# Controller.net
KiCad netlist of a schematic drawn in EAGLE
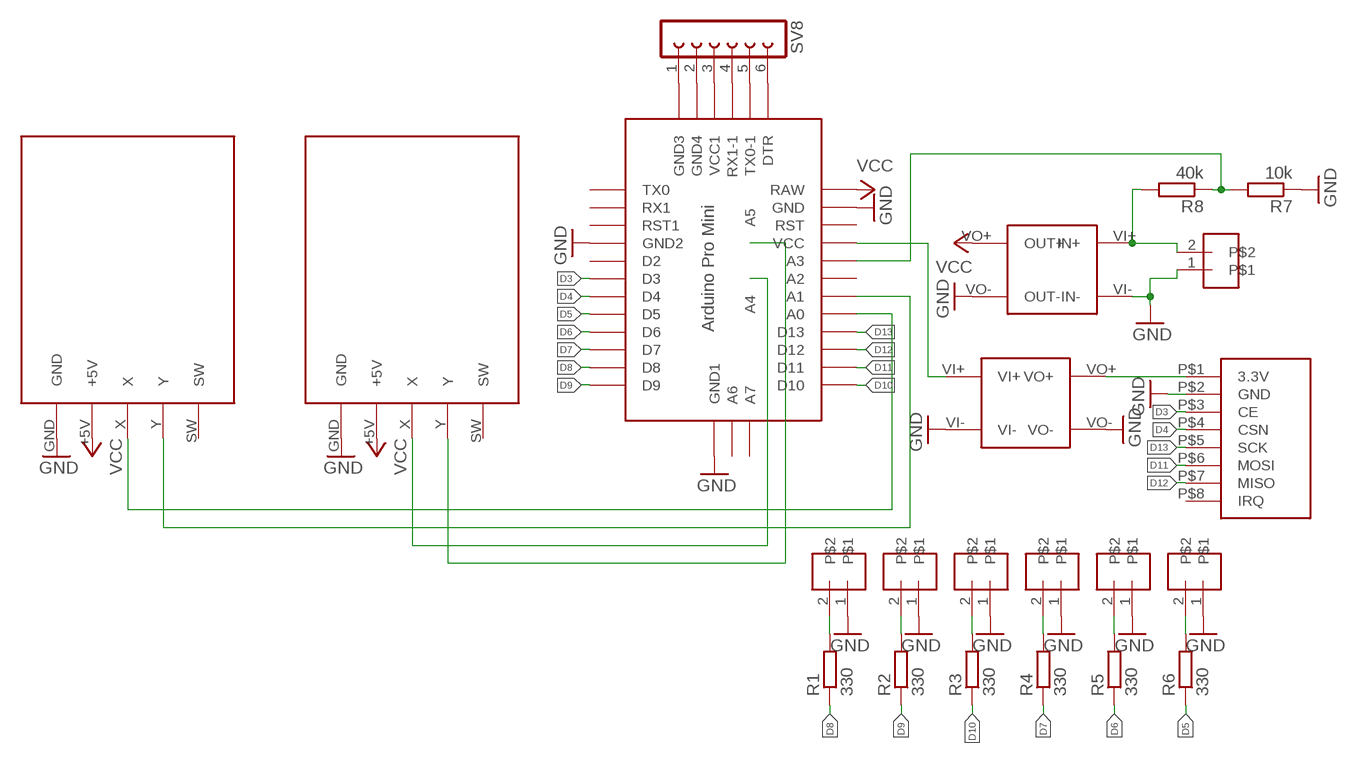
[diagram p0: schematic, sheet 1]

(export (version "E")
  (design (tool "Eeschema 10.0.6"))
  (components
    (comp (ref "R1")
      (value "330")
      (footprint "eagle-import:R1206")
      (libsource (lib "eagle-import") (part "R-EU_R1206"))
    )
    (comp (ref "R2")
      (value "330")
      (footprint "eagle-import:R1206")
      (libsource (lib "eagle-import") (part "R-EU_R1206"))
    )
    (comp (ref "R3")
      (value "330")
      (footprint "eagle-import:R1206")
      (libsource (lib "eagle-import") (part "R-EU_R1206"))
    )
    (comp (ref "R4")
      (value "330")
      (footprint "eagle-import:R1206")
      (libsource (lib "eagle-import") (part "R-EU_R1206"))
    )
    (comp (ref "R5")
      (value "330")
      (footprint "eagle-import:R1206")
      (libsource (lib "eagle-import") (part "R-EU_R1206"))
    )
    (comp (ref "R6")
      (value "330")
      (footprint "eagle-import:R1206")
      (libsource (lib "eagle-import") (part "R-EU_R1206"))
    )
    (comp (ref "R7")
      (value "10k")
      (footprint "eagle-import:R1206")
      (libsource (lib "eagle-import") (part "R-EU_R1206"))
    )
    (comp (ref "R8")
      (value "40k")
      (footprint "eagle-import:R1206")
      (libsource (lib "eagle-import") (part "R-EU_R1206"))
    )
    (comp (ref "SV1")
      (value "FE05-1")
      (footprint "eagle-import:FE05-1")
      (libsource (lib "eagle-import") (part "FE05-1"))
    )
    (comp (ref "SV2")
      (value "FE05-1")
      (footprint "eagle-import:FE05-1")
      (libsource (lib "eagle-import") (part "FE05-1"))
    )
    (comp (ref "SV3")
      (value "FE05-1")
      (footprint "eagle-import:FE05-1")
      (libsource (lib "eagle-import") (part "FE05-1"))
    )
    (comp (ref "SV4")
      (value "FE05-1")
      (footprint "eagle-import:FE05-1")
      (libsource (lib "eagle-import") (part "FE05-1"))
    )
    (comp (ref "SV5")
      (value "FE05-1")
      (footprint "eagle-import:FE05-1")
      (libsource (lib "eagle-import") (part "FE05-1"))
    )
    (comp (ref "SV6")
      (value "FE05-1")
      (footprint "eagle-import:FE05-1")
      (libsource (lib "eagle-import") (part "FE05-1"))
    )
    (comp (ref "SV7")
      (value "FE05-1")
      (footprint "eagle-import:FE05-1")
      (libsource (lib "eagle-import") (part "FE05-1"))
    )
    (comp (ref "SV8")
      (value "FE06-1")
      (footprint "eagle-import:FE06")
      (libsource (lib "eagle-import") (part "FE06-1"))
    )
    (comp (ref "U$1")
      (value "JOYSTICK")
      (footprint "eagle-import:JOYSTICK")
      (libsource (lib "eagle-import") (part "JOYSTICK"))
    )
    (comp (ref "U$2")
      (value "JOYSTICK")
      (footprint "eagle-import:JOYSTICK")
      (libsource (lib "eagle-import") (part "JOYSTICK"))
    )
    (comp (ref "U$4")
      (value "ABK-PRO-MINI")
      (footprint "eagle-import:ABK-PRO-MINI")
      (libsource (lib "eagle-import") (part "ABK-PRO-MINI"))
    )
    (comp (ref "U$5")
      (value "NRF24L01")
      (footprint "eagle-import:NRF24L01")
      (libsource (lib "eagle-import") (part "NRF24L01"))
    )
    (comp (ref "U$7")
      (value "3.3V")
      (footprint "eagle-import:3.3V")
      (libsource (lib "eagle-import") (part "3.3V"))
    )
    (comp (ref "U$8") (value "5V") (footprint "eagle-import:5V") (libsource (lib "eagle-import") (part "5V")))
  )
  (nets
    (net (code "1") (name "D3") (class "Default")
      (node (ref "U$4") (pin "P$12") (pinfunction "D3_P$12") (pintype "bidirectional"))
      (node (ref "U$5") (pin "P$3") (pinfunction "CE_P$3") (pintype "bidirectional"))
    )
    (net (code "2") (name "D4") (class "Default")
      (node (ref "U$4") (pin "P$13") (pinfunction "D4_P$13") (pintype "bidirectional"))
      (node (ref "U$5") (pin "P$4") (pinfunction "CSN_P$4") (pintype "bidirectional"))
    )
    (net (code "3") (name "D5") (class "Default")
      (node (ref "R6") (pin "1") (pinfunction "1_1") (pintype "passive"))
      (node (ref "U$4") (pin "P$14") (pinfunction "D5_P$14") (pintype "bidirectional"))
    )
    (net (code "4") (name "D6") (class "Default")
      (node (ref "R5") (pin "1") (pinfunction "1_1") (pintype "passive"))
      (node (ref "U$4") (pin "P$15") (pinfunction "D6_P$15") (pintype "bidirectional"))
    )
    (net (code "5") (name "D7") (class "Default")
      (node (ref "R4") (pin "1") (pinfunction "1_1") (pintype "passive"))
      (node (ref "U$4") (pin "P$16") (pinfunction "D7_P$16") (pintype "bidirectional"))
    )
    (net (code "6") (name "D8") (class "Default")
      (node (ref "R1") (pin "1") (pinfunction "1_1") (pintype "passive"))
      (node (ref "U$4") (pin "P$17") (pinfunction "D8_P$17") (pintype "bidirectional"))
    )
    (net (code "7") (name "D9") (class "Default")
      (node (ref "R2") (pin "1") (pinfunction "1_1") (pintype "passive"))
      (node (ref "U$4") (pin "P$18") (pinfunction "D9_P$18") (pintype "bidirectional"))
    )
    (net (code "8") (name "D10") (class "Default")
      (node (ref "R3") (pin "1") (pinfunction "1_1") (pintype "passive"))
      (node (ref "U$4") (pin "P$30") (pinfunction "D10_P$30") (pintype "bidirectional"))
    )
    (net (code "9") (name "D11") (class "Default")
      (node (ref "U$4") (pin "P$29") (pinfunction "D11_P$29") (pintype "bidirectional"))
      (node (ref "U$5") (pin "P$6") (pinfunction "MOSI_P$6") (pintype "bidirectional"))
    )
    (net (code "10") (name "D12") (class "Default")
      (node (ref "U$4") (pin "P$28") (pinfunction "D12_P$28") (pintype "bidirectional"))
      (node (ref "U$5") (pin "P$7") (pinfunction "MISO_P$7") (pintype "bidirectional"))
    )
    (net (code "11") (name "D13") (class "Default")
      (node (ref "U$4") (pin "P$27") (pinfunction "D13_P$27") (pintype "bidirectional"))
      (node (ref "U$5") (pin "P$5") (pinfunction "SCK_P$5") (pintype "bidirectional"))
    )
    (net (code "12") (name "GND") (class "Default")
      (node (ref "R7") (pin "1") (pinfunction "1_1") (pintype "passive"))
      (node (ref "SV1") (pin "1") (pinfunction "P$1_1") (pintype "bidirectional"))
      (node (ref "SV2") (pin "1") (pinfunction "P$1_1") (pintype "bidirectional"))
      (node (ref "SV3") (pin "1") (pinfunction "P$1_1") (pintype "bidirectional"))
      (node (ref "SV4") (pin "1") (pinfunction "P$1_1") (pintype "bidirectional"))
      (node (ref "SV5") (pin "1") (pinfunction "P$1_1") (pintype "bidirectional"))
      (node (ref "SV6") (pin "1") (pinfunction "P$1_1") (pintype "bidirectional"))
      (node (ref "SV7") (pin "1") (pinfunction "P$1_1") (pintype "bidirectional"))
      (node (ref "U$1") (pin "GND") (pinfunction "GND_GND") (pintype "bidirectional"))
      (node (ref "U$2") (pin "GND") (pinfunction "GND_GND") (pintype "bidirectional"))
      (node (ref "U$4") (pin "P$10") (pinfunction "GND2_P$10") (pintype "bidirectional"))
      (node (ref "U$4") (pin "P$20") (pinfunction "GND_P$20") (pintype "bidirectional"))
      (node (ref "U$4") (pin "P$33") (pinfunction "GND1_P$33") (pintype "bidirectional"))
      (node (ref "U$5") (pin "P$2") (pinfunction "GND_P$2") (pintype "bidirectional"))
      (node (ref "U$7") (pin "VI-") (pinfunction "VI-_VI-") (pintype "bidirectional"))
      (node (ref "U$7") (pin "VO-") (pinfunction "VO-_VO-") (pintype "bidirectional"))
      (node (ref "U$8") (pin "VI-") (pinfunction "IN-_VI-") (pintype "bidirectional"))
      (node (ref "U$8") (pin "VO-") (pinfunction "OUT-_VO-") (pintype "bidirectional"))
    )
    (net (code "13") (name "Net-(SV1-P$2)") (class "Default")
      (node (ref "R8") (pin "2") (pinfunction "2_2") (pintype "passive"))
      (node (ref "SV1") (pin "2") (pinfunction "P$2_2") (pintype "bidirectional"))
      (node (ref "U$8") (pin "VI+") (pinfunction "IN+_VI+") (pintype "bidirectional"))
    )
    (net (code "14") (name "Net-(SV2-P$2)") (class "Default")
      (node (ref "R6") (pin "2") (pinfunction "2_2") (pintype "passive"))
      (node (ref "SV2") (pin "2") (pinfunction "P$2_2") (pintype "bidirectional"))
    )
    (net (code "15") (name "Net-(SV3-P$2)") (class "Default")
      (node (ref "R5") (pin "2") (pinfunction "2_2") (pintype "passive"))
      (node (ref "SV3") (pin "2") (pinfunction "P$2_2") (pintype "bidirectional"))
    )
    (net (code "16") (name "Net-(SV4-P$2)") (class "Default")
      (node (ref "R4") (pin "2") (pinfunction "2_2") (pintype "passive"))
      (node (ref "SV4") (pin "2") (pinfunction "P$2_2") (pintype "bidirectional"))
    )
    (net (code "17") (name "Net-(SV5-P$2)") (class "Default")
      (node (ref "R3") (pin "2") (pinfunction "2_2") (pintype "passive"))
      (node (ref "SV5") (pin "2") (pinfunction "P$2_2") (pintype "bidirectional"))
    )
    (net (code "18") (name "Net-(SV6-P$2)") (class "Default")
      (node (ref "R2") (pin "2") (pinfunction "2_2") (pintype "passive"))
      (node (ref "SV6") (pin "2") (pinfunction "P$2_2") (pintype "bidirectional"))
    )
    (net (code "19") (name "Net-(SV7-P$2)") (class "Default")
      (node (ref "R1") (pin "2") (pinfunction "2_2") (pintype "passive"))
      (node (ref "SV7") (pin "2") (pinfunction "P$2_2") (pintype "bidirectional"))
    )
    (net (code "20") (name "Net-(U$4-A0)") (class "Default")
      (node (ref "U$1") (pin "X") (pinfunction "X_X") (pintype "bidirectional"))
      (node (ref "U$4") (pin "P$26") (pinfunction "A0_P$26") (pintype "bidirectional"))
    )
    (net (code "21") (name "Net-(U$4-A1)") (class "Default")
      (node (ref "U$1") (pin "Y") (pinfunction "Y_Y") (pintype "bidirectional"))
      (node (ref "U$4") (pin "P$25") (pinfunction "A1_P$25") (pintype "bidirectional"))
    )
    (net (code "22") (name "Net-(U$4-A3)") (class "Default")
      (node (ref "R7") (pin "2") (pinfunction "2_2") (pintype "passive"))
      (node (ref "R8") (pin "1") (pinfunction "1_1") (pintype "passive"))
      (node (ref "U$4") (pin "P$23") (pinfunction "A3_P$23") (pintype "bidirectional"))
    )
    (net (code "23") (name "Net-(U$4-A4)") (class "Default")
      (node (ref "U$2") (pin "X") (pinfunction "X_X") (pintype "bidirectional"))
      (node (ref "U$4") (pin "P$35") (pinfunction "A4_P$35") (pintype "bidirectional"))
    )
    (net (code "24") (name "Net-(U$4-A5)") (class "Default")
      (node (ref "U$2") (pin "Y") (pinfunction "Y_Y") (pintype "bidirectional"))
      (node (ref "U$4") (pin "P$34") (pinfunction "A5_P$34") (pintype "bidirectional"))
    )
    (net (code "25") (name "Net-(U$4-DTR)") (class "Default")
      (node (ref "SV8") (pin "6") (pinfunction "6_6") (pintype "passive"))
      (node (ref "U$4") (pin "P$6") (pinfunction "DTR_P$6") (pintype "bidirectional"))
    )
    (net (code "26") (name "Net-(U$4-GND3)") (class "Default")
      (node (ref "SV8") (pin "1") (pinfunction "1_1") (pintype "passive"))
      (node (ref "U$4") (pin "P$1") (pinfunction "GND3_P$1") (pintype "bidirectional"))
    )
    (net (code "27") (name "Net-(U$4-GND4)") (class "Default")
      (node (ref "SV8") (pin "2") (pinfunction "2_2") (pintype "passive"))
      (node (ref "U$4") (pin "P$2") (pinfunction "GND4_P$2") (pintype "bidirectional"))
    )
    (net (code "28") (name "Net-(U$4-RX1-1)") (class "Default")
      (node (ref "SV8") (pin "4") (pinfunction "4_4") (pintype "passive"))
      (node (ref "U$4") (pin "P$4") (pinfunction "RX1-1_P$4") (pintype "bidirectional"))
    )
    (net (code "29") (name "Net-(U$4-TX0-1)") (class "Default")
      (node (ref "SV8") (pin "5") (pinfunction "5_5") (pintype "passive"))
      (node (ref "U$4") (pin "P$5") (pinfunction "TX0-1_P$5") (pintype "bidirectional"))
    )
    (net (code "30") (name "Net-(U$4-VCC)") (class "Default")
      (node (ref "U$4") (pin "P$22") (pinfunction "VCC_P$22") (pintype "bidirectional"))
      (node (ref "U$7") (pin "VI+") (pinfunction "VI+_VI+") (pintype "bidirectional"))
    )
    (net (code "31") (name "Net-(U$4-VCC1)") (class "Default")
      (node (ref "SV8") (pin "3") (pinfunction "3_3") (pintype "passive"))
      (node (ref "U$4") (pin "P$3") (pinfunction "VCC1_P$3") (pintype "bidirectional"))
    )
    (net (code "32") (name "Net-(U$5-3.3V)") (class "Default")
      (node (ref "U$5") (pin "P$1") (pinfunction "3.3V_P$1") (pintype "bidirectional"))
      (node (ref "U$7") (pin "VO+") (pinfunction "VO+_VO+") (pintype "bidirectional"))
    )
    (net (code "33") (name "VCC") (class "Default")
      (node (ref "U$1") (pin "+5V") (pinfunction "+5V_+5V") (pintype "bidirectional"))
      (node (ref "U$2") (pin "+5V") (pinfunction "+5V_+5V") (pintype "bidirectional"))
      (node (ref "U$4") (pin "P$19") (pinfunction "RAW_P$19") (pintype "bidirectional"))
      (node (ref "U$8") (pin "VO+") (pinfunction "OUT+_VO+") (pintype "bidirectional"))
    )
    (net (code "34") (name "unconnected-(U$1-PadSW)") (class "Default")
      (node (ref "U$1") (pin "SW") (pinfunction "SW_SW") (pintype "bidirectional"))
    )
    (net (code "35") (name "unconnected-(U$2-PadSW)") (class "Default")
      (node (ref "U$2") (pin "SW") (pinfunction "SW_SW") (pintype "bidirectional"))
    )
    (net (code "36") (name "unconnected-(U$4-A2-PadP$24)") (class "Default")
      (node (ref "U$4") (pin "P$24") (pinfunction "A2_P$24") (pintype "bidirectional"))
    )
    (net (code "37") (name "unconnected-(U$4-A6-PadP$32)") (class "Default")
      (node (ref "U$4") (pin "P$32") (pinfunction "A6_P$32") (pintype "bidirectional"))
    )
    (net (code "38") (name "unconnected-(U$4-A7-PadP$31)") (class "Default")
      (node (ref "U$4") (pin "P$31") (pinfunction "A7_P$31") (pintype "bidirectional"))
    )
    (net (code "39") (name "unconnected-(U$4-D2-PadP$11)") (class "Default")
      (node (ref "U$4") (pin "P$11") (pinfunction "D2_P$11") (pintype "bidirectional"))
    )
    (net (code "40") (name "unconnected-(U$4-RST-PadP$21)") (class "Default")
      (node (ref "U$4") (pin "P$21") (pinfunction "RST_P$21") (pintype "bidirectional"))
    )
    (net (code "41") (name "unconnected-(U$4-RST1-PadP$9)") (class "Default")
      (node (ref "U$4") (pin "P$9") (pinfunction "RST1_P$9") (pintype "bidirectional"))
    )
    (net (code "42") (name "unconnected-(U$4-RX1-PadP$8)") (class "Default")
      (node (ref "U$4") (pin "P$8") (pinfunction "RX1_P$8") (pintype "bidirectional"))
    )
    (net (code "43") (name "unconnected-(U$4-TX0-PadP$7)") (class "Default")
      (node (ref "U$4") (pin "P$7") (pinfunction "TX0_P$7") (pintype "bidirectional"))
    )
    (net (code "44") (name "unconnected-(U$5-IRQ-PadP$8)") (class "Default")
      (node (ref "U$5") (pin "P$8") (pinfunction "IRQ_P$8") (pintype "bidirectional"))
    )
  )
)
